# power_1.net
KiCad netlist of a schematic drawn in Altium Designer
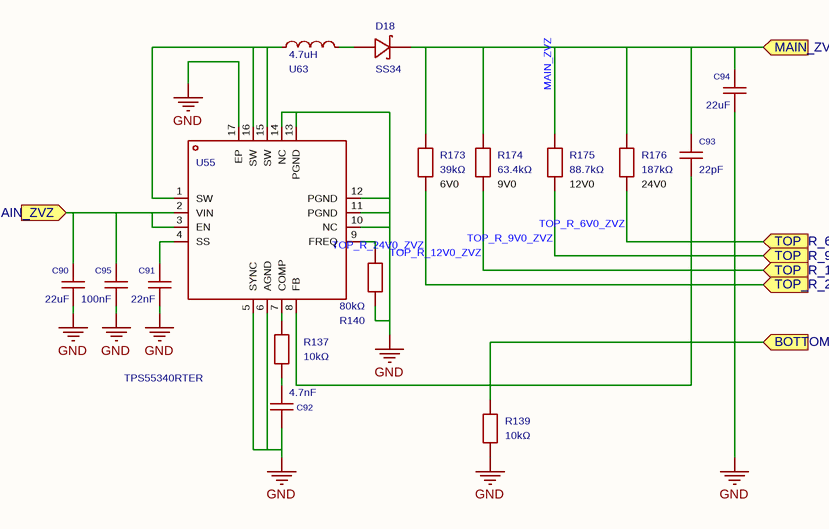
[diagram p0: power_1.schdoc]

(export (version "E")
  (design (tool "Eeschema 10.0.6"))
  (components
    (comp (ref "C90")
      (value "22uF")
      (footprint "C0603")
      (description "Capacitance:22nF Tolerance:±10% Tolerance:±10% Voltage Rating:50V Temperature Coefficient:X7R")
      (fields
        (field (name "MANUFACTURER PART") "CL10B223KB8NNNC")
        (field (name "MANUFACTURER") "SAMSUNG(三星)")
      )
      (libsource (lib "altium-import") (part "root_1_CL10B223KB8NNNC_"))
    )
    (comp (ref "C91")
      (value "22nF")
      (footprint "C0603")
      (description "Capacitance:22nF Tolerance:±10% Tolerance:±10% Voltage Rating:50V Temperature Coefficient:X7R")
      (fields
        (field (name "MANUFACTURER PART") "CL10B223KB8NNNC")
        (field (name "MANUFACTURER") "SAMSUNG(三星)")
      )
      (libsource (lib "altium-import") (part "root_1_CL10B223KB8NNNC_"))
    )
    (comp (ref "C92")
      (value "4.7nF")
      (footprint "C0603")
      (description "Capacitance:22nF Tolerance:±10% Tolerance:±10% Voltage Rating:50V Temperature Coefficient:X7R")
      (fields
        (field (name "MANUFACTURER PART") "CL10B223KB8NNNC")
        (field (name "MANUFACTURER") "SAMSUNG(三星)")
      )
      (libsource (lib "altium-import") (part "root_1_CL10B223KB8NNNC_"))
    )
    (comp (ref "C93")
      (value "22pF")
      (footprint "C0603")
      (description "Capacitance:22nF Tolerance:±10% Tolerance:±10% Voltage Rating:50V Temperature Coefficient:X7R")
      (fields
        (field (name "MANUFACTURER PART") "CL10B223KB8NNNC")
        (field (name "MANUFACTURER") "SAMSUNG(三星)")
      )
      (libsource (lib "altium-import") (part "root_1_CL10B223KB8NNNC_"))
    )
    (comp (ref "C94")
      (value "22uF")
      (footprint "C0603")
      (description "Capacitance:22nF Tolerance:±10% Tolerance:±10% Voltage Rating:50V Temperature Coefficient:X7R")
      (fields
        (field (name "MANUFACTURER PART") "CL10B223KB8NNNC")
        (field (name "MANUFACTURER") "SAMSUNG(三星)")
      )
      (libsource (lib "altium-import") (part "root_1_CL10B223KB8NNNC_"))
    )
    (comp (ref "C95")
      (value "100nF")
      (footprint "C0603")
      (description "Capacitance:22nF Tolerance:±10% Tolerance:±10% Voltage Rating:50V Temperature Coefficient:X7R")
      (fields
        (field (name "MANUFACTURER PART") "CL10B223KB8NNNC")
        (field (name "MANUFACTURER") "SAMSUNG(三星)")
      )
      (libsource (lib "altium-import") (part "root_1_CL10B223KB8NNNC_"))
    )
    (comp (ref "D18")
      (value "SS34")
      (footprint "SMA_L4.3-W2.6-LS5.2-RD")
      (fields (field (name "MANUFACTURER") "MDD(辰达半导体)"))
      (libsource (lib "altium-import") (part "root_0_mirrored_SS34_C8678_"))
    )
    (comp (ref "R137")
      (value "10kΩ")
      (footprint "R0402")
      (fields
        (field (name "MANUFACTURER") "FOJAN(富捷)")
        (field (name "MANUFACTURERPART") "FRC0402F3002TS")
        (field (name "TOLERANCE") "±1%")
      )
      (libsource (lib "altium-import") (part "root_3_FRC0402F3002TS_"))
    )
    (comp (ref "R139")
      (value "10kΩ")
      (footprint "R0402")
      (fields
        (field (name "MANUFACTURER") "FOJAN(富捷)")
        (field (name "MANUFACTURERPART") "FRC0402F3002TS")
        (field (name "TOLERANCE") "±1%")
      )
      (libsource (lib "altium-import") (part "root_3_FRC0402F3002TS_"))
    )
    (comp (ref "R140")
      (value "80kΩ")
      (footprint "R0402")
      (fields
        (field (name "MANUFACTURER") "FOJAN(富捷)")
        (field (name "MANUFACTURERPART") "FRC0402F3002TS")
        (field (name "TOLERANCE") "±1%")
      )
      (libsource (lib "altium-import") (part "root_3_FRC0402F3002TS_"))
    )
    (comp (ref "R173")
      (value "39kΩ")
      (footprint "R0402")
      (fields
        (field (name "MANUFACTURER") "FOJAN(富捷)")
        (field (name "MANUFACTURERPART") "FRC0402F3002TS")
        (field (name "TOLERANCE") "±1%")
      )
      (libsource (lib "altium-import") (part "root_3_FRC0402F3002TS_"))
    )
    (comp (ref "R174")
      (value "63.4kΩ")
      (footprint "R0402")
      (fields
        (field (name "MANUFACTURER") "FOJAN(富捷)")
        (field (name "MANUFACTURERPART") "FRC0402F3002TS")
        (field (name "TOLERANCE") "±1%")
      )
      (libsource (lib "altium-import") (part "root_3_FRC0402F3002TS_"))
    )
    (comp (ref "R175")
      (value "88.7kΩ")
      (footprint "R0402")
      (fields
        (field (name "MANUFACTURER") "FOJAN(富捷)")
        (field (name "MANUFACTURERPART") "FRC0402F3002TS")
        (field (name "TOLERANCE") "±1%")
      )
      (libsource (lib "altium-import") (part "root_3_FRC0402F3002TS_"))
    )
    (comp (ref "R176")
      (value "187kΩ")
      (footprint "R0402")
      (fields
        (field (name "MANUFACTURER") "FOJAN(富捷)")
        (field (name "MANUFACTURERPART") "FRC0402F3002TS")
        (field (name "TOLERANCE") "±1%")
      )
      (libsource (lib "altium-import") (part "root_3_FRC0402F3002TS_"))
    )
    (comp (ref "U55")
      (value "TPS55340RTER")
      (footprint "VQFN-16_L3.0-W3.0-P0.50-BL-EP1.7")
      (fields (field (name "MANUFACTURER") "TI(德州仪器)"))
      (libsource (lib "altium-import") (part "root_0_TPS55340RTER_"))
    )
    (comp (ref "U63")
      (value "4.7uH")
      (footprint "IND-SMD_L2.5-W2.0_YXMBL252010P")
      (fields
        (field (name "MANUFACTURER") "APV(爱普微)")
        (field (name "MANUFACTURERPART") "APH252010T2R2M")
        (field (name "TOLERANCE") "±20%")
      )
      (libsource (lib "altium-import") (part "root_0_APH252010T2R2M_"))
    )
  )
  (nets
    (net (code "1") (name "/BOTTOM_R_ZVZ") (class "Default")
      (node (ref "C93") (pin "1") (pinfunction "1_1") (pintype "passive"))
      (node (ref "R139") (pin "1") (pinfunction "1_1") (pintype "passive"))
      (node (ref "U55") (pin "8") (pinfunction "FB_8") (pintype "passive"))
    )
    (net (code "2") (name "/MAIN_ZVZ") (class "Default")
      (node (ref "C90") (pin "2") (pinfunction "2_2") (pintype "passive"))
      (node (ref "C93") (pin "2") (pinfunction "2_2") (pintype "passive"))
      (node (ref "C94") (pin "2") (pinfunction "2_2") (pintype "passive"))
      (node (ref "C95") (pin "2") (pinfunction "2_2") (pintype "passive"))
      (node (ref "D18") (pin "1") (pinfunction "K_1") (pintype "passive"))
      (node (ref "R173") (pin "1") (pinfunction "1_1") (pintype "passive"))
      (node (ref "R174") (pin "1") (pinfunction "1_1") (pintype "passive"))
      (node (ref "R175") (pin "1") (pinfunction "1_1") (pintype "passive"))
      (node (ref "R176") (pin "1") (pinfunction "1_1") (pintype "passive"))
      (node (ref "U55") (pin "2") (pinfunction "VIN_2") (pintype "passive"))
      (node (ref "U55") (pin "3") (pinfunction "EN_3") (pintype "passive"))
    )
    (net (code "3") (name "/TOP_R_6V0_ZVZ") (class "Default")
      (node (ref "R176") (pin "2") (pinfunction "2_2") (pintype "passive"))
    )
    (net (code "4") (name "/TOP_R_9V0_ZVZ") (class "Default")
      (node (ref "R175") (pin "2") (pinfunction "2_2") (pintype "passive"))
    )
    (net (code "5") (name "/TOP_R_12V0_ZVZ") (class "Default")
      (node (ref "R174") (pin "2") (pinfunction "2_2") (pintype "passive"))
    )
    (net (code "6") (name "/TOP_R_24V0_ZVZ") (class "Default")
      (node (ref "R173") (pin "2") (pinfunction "2_2") (pintype "passive"))
    )
    (net (code "7") (name "GND") (class "Default")
      (node (ref "C90") (pin "1") (pinfunction "1_1") (pintype "passive"))
      (node (ref "C91") (pin "1") (pinfunction "1_1") (pintype "passive"))
      (node (ref "C92") (pin "1") (pinfunction "1_1") (pintype "passive"))
      (node (ref "C94") (pin "1") (pinfunction "1_1") (pintype "passive"))
      (node (ref "C95") (pin "1") (pinfunction "1_1") (pintype "passive"))
      (node (ref "R139") (pin "2") (pinfunction "2_2") (pintype "passive"))
      (node (ref "R140") (pin "2") (pinfunction "2_2") (pintype "passive"))
      (node (ref "U55") (pin "10") (pinfunction "NC_10") (pintype "passive"))
      (node (ref "U55") (pin "11") (pinfunction "PGND_11") (pintype "passive"))
      (node (ref "U55") (pin "12") (pinfunction "PGND_12") (pintype "passive"))
      (node (ref "U55") (pin "13") (pinfunction "PGND_13") (pintype "passive"))
      (node (ref "U55") (pin "14") (pinfunction "NC_14") (pintype "passive"))
      (node (ref "U55") (pin "17") (pinfunction "EP_17") (pintype "passive"))
      (node (ref "U55") (pin "5") (pinfunction "SYNC_5") (pintype "passive"))
      (node (ref "U55") (pin "6") (pinfunction "AGND_6") (pintype "passive"))
    )
    (net (code "8") (name "Net-(C92-Pad2)") (class "Default")
      (node (ref "C92") (pin "2") (pinfunction "2_2") (pintype "passive"))
      (node (ref "R137") (pin "2") (pinfunction "2_2") (pintype "passive"))
    )
    (net (code "9") (name "Net-(D18-A)") (class "Default")
      (node (ref "D18") (pin "2") (pinfunction "A_2") (pintype "passive"))
      (node (ref "U63") (pin "2") (pinfunction "2_2") (pintype "passive"))
    )
    (net (code "10") (name "Net-(U55-COMP)") (class "Default")
      (node (ref "R137") (pin "1") (pinfunction "1_1") (pintype "passive"))
      (node (ref "U55") (pin "7") (pinfunction "COMP_7") (pintype "passive"))
    )
    (net (code "11") (name "Net-(U55-FREQ)") (class "Default")
      (node (ref "R140") (pin "1") (pinfunction "1_1") (pintype "passive"))
      (node (ref "U55") (pin "9") (pinfunction "FREQ_9") (pintype "passive"))
    )
    (net (code "12") (name "Net-(U55-SS)") (class "Default")
      (node (ref "C91") (pin "2") (pinfunction "2_2") (pintype "passive"))
      (node (ref "U55") (pin "4") (pinfunction "SS_4") (pintype "passive"))
    )
    (net (code "13") (name "Net-(U55-SW-Pad1)") (class "Default")
      (node (ref "U55") (pin "1") (pinfunction "SW_1") (pintype "passive"))
      (node (ref "U55") (pin "15") (pinfunction "SW_15") (pintype "passive"))
      (node (ref "U55") (pin "16") (pinfunction "SW_16") (pintype "passive"))
      (node (ref "U63") (pin "1") (pinfunction "1_1") (pintype "passive"))
    )
  )
)
